# SharpIR_Filt.net
KiCad netlist of a schematic drawn in EAGLE
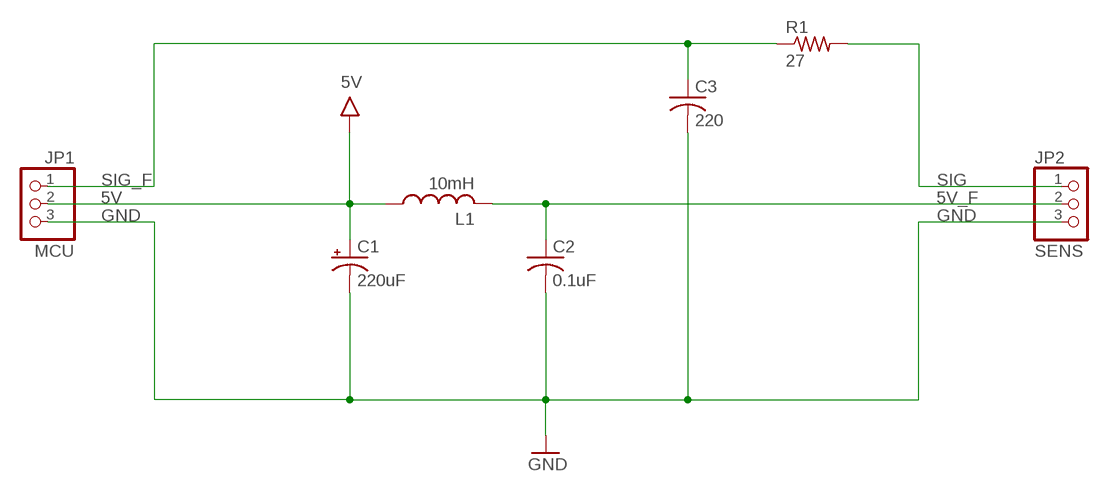
[diagram p0: schematic, sheet 1]

(export (version "E")
  (design (tool "Eeschema 10.0.6"))
  (components
    (comp (ref "C1")
      (value "220uF")
      (footprint "eagle-import:PANASONIC_C")
      (libsource (lib "eagle-import") (part "CPOL-USC"))
    )
    (comp (ref "C2")
      (value "0.1uF")
      (footprint "eagle-import:C0603")
      (libsource (lib "eagle-import") (part "C-USC0603"))
    )
    (comp (ref "C3")
      (value "220")
      (footprint "eagle-import:C0603")
      (libsource (lib "eagle-import") (part "C-USC0603"))
    )
    (comp (ref "JP1")
      (value "MCU")
      (footprint "eagle-import:1X03M")
      (libsource (lib "eagle-import") (part "PINHD-1X03_2.00"))
    )
    (comp (ref "JP2")
      (value "SENS")
      (footprint "eagle-import:1X03M")
      (libsource (lib "eagle-import") (part "PINHD-1X03_2.00"))
    )
    (comp (ref "L1")
      (value "10mH")
      (footprint "eagle-import:L5650M")
      (libsource (lib "eagle-import") (part "L-USL5650M"))
    )
    (comp (ref "R1")
      (value "27")
      (footprint "eagle-import:R0603")
      (libsource (lib "eagle-import") (part "R-US_R0603"))
    )
  )
  (nets
    (net (code "1") (name "/5V_F") (class "Default")
      (node (ref "C2") (pin "1") (pinfunction "1_1") (pintype "passive"))
      (node (ref "JP2") (pin "2") (pinfunction "2_2") (pintype "passive"))
      (node (ref "L1") (pin "2") (pinfunction "2_2") (pintype "passive"))
    )
    (net (code "2") (name "/SIG") (class "Default")
      (node (ref "JP2") (pin "1") (pinfunction "1_1") (pintype "passive"))
      (node (ref "R1") (pin "2") (pinfunction "2_2") (pintype "passive"))
    )
    (net (code "3") (name "/SIG_F") (class "Default")
      (node (ref "C3") (pin "1") (pinfunction "1_1") (pintype "passive"))
      (node (ref "JP1") (pin "1") (pinfunction "1_1") (pintype "passive"))
      (node (ref "R1") (pin "1") (pinfunction "1_1") (pintype "passive"))
    )
    (net (code "4") (name "5V") (class "Default")
      (node (ref "C1") (pin "+") (pinfunction "+_+") (pintype "passive"))
      (node (ref "JP1") (pin "2") (pinfunction "2_2") (pintype "passive"))
      (node (ref "L1") (pin "1") (pinfunction "1_1") (pintype "passive"))
    )
    (net (code "5") (name "GND") (class "Default")
      (node (ref "C1") (pin "-") (pinfunction "-_-") (pintype "passive"))
      (node (ref "C2") (pin "2") (pinfunction "2_2") (pintype "passive"))
      (node (ref "C3") (pin "2") (pinfunction "2_2") (pintype "passive"))
      (node (ref "JP1") (pin "3") (pinfunction "3_3") (pintype "passive"))
      (node (ref "JP2") (pin "3") (pinfunction "3_3") (pintype "passive"))
    )
  )
)
